# two_tone__2.net
KiCad netlist of a schematic drawn in EAGLE
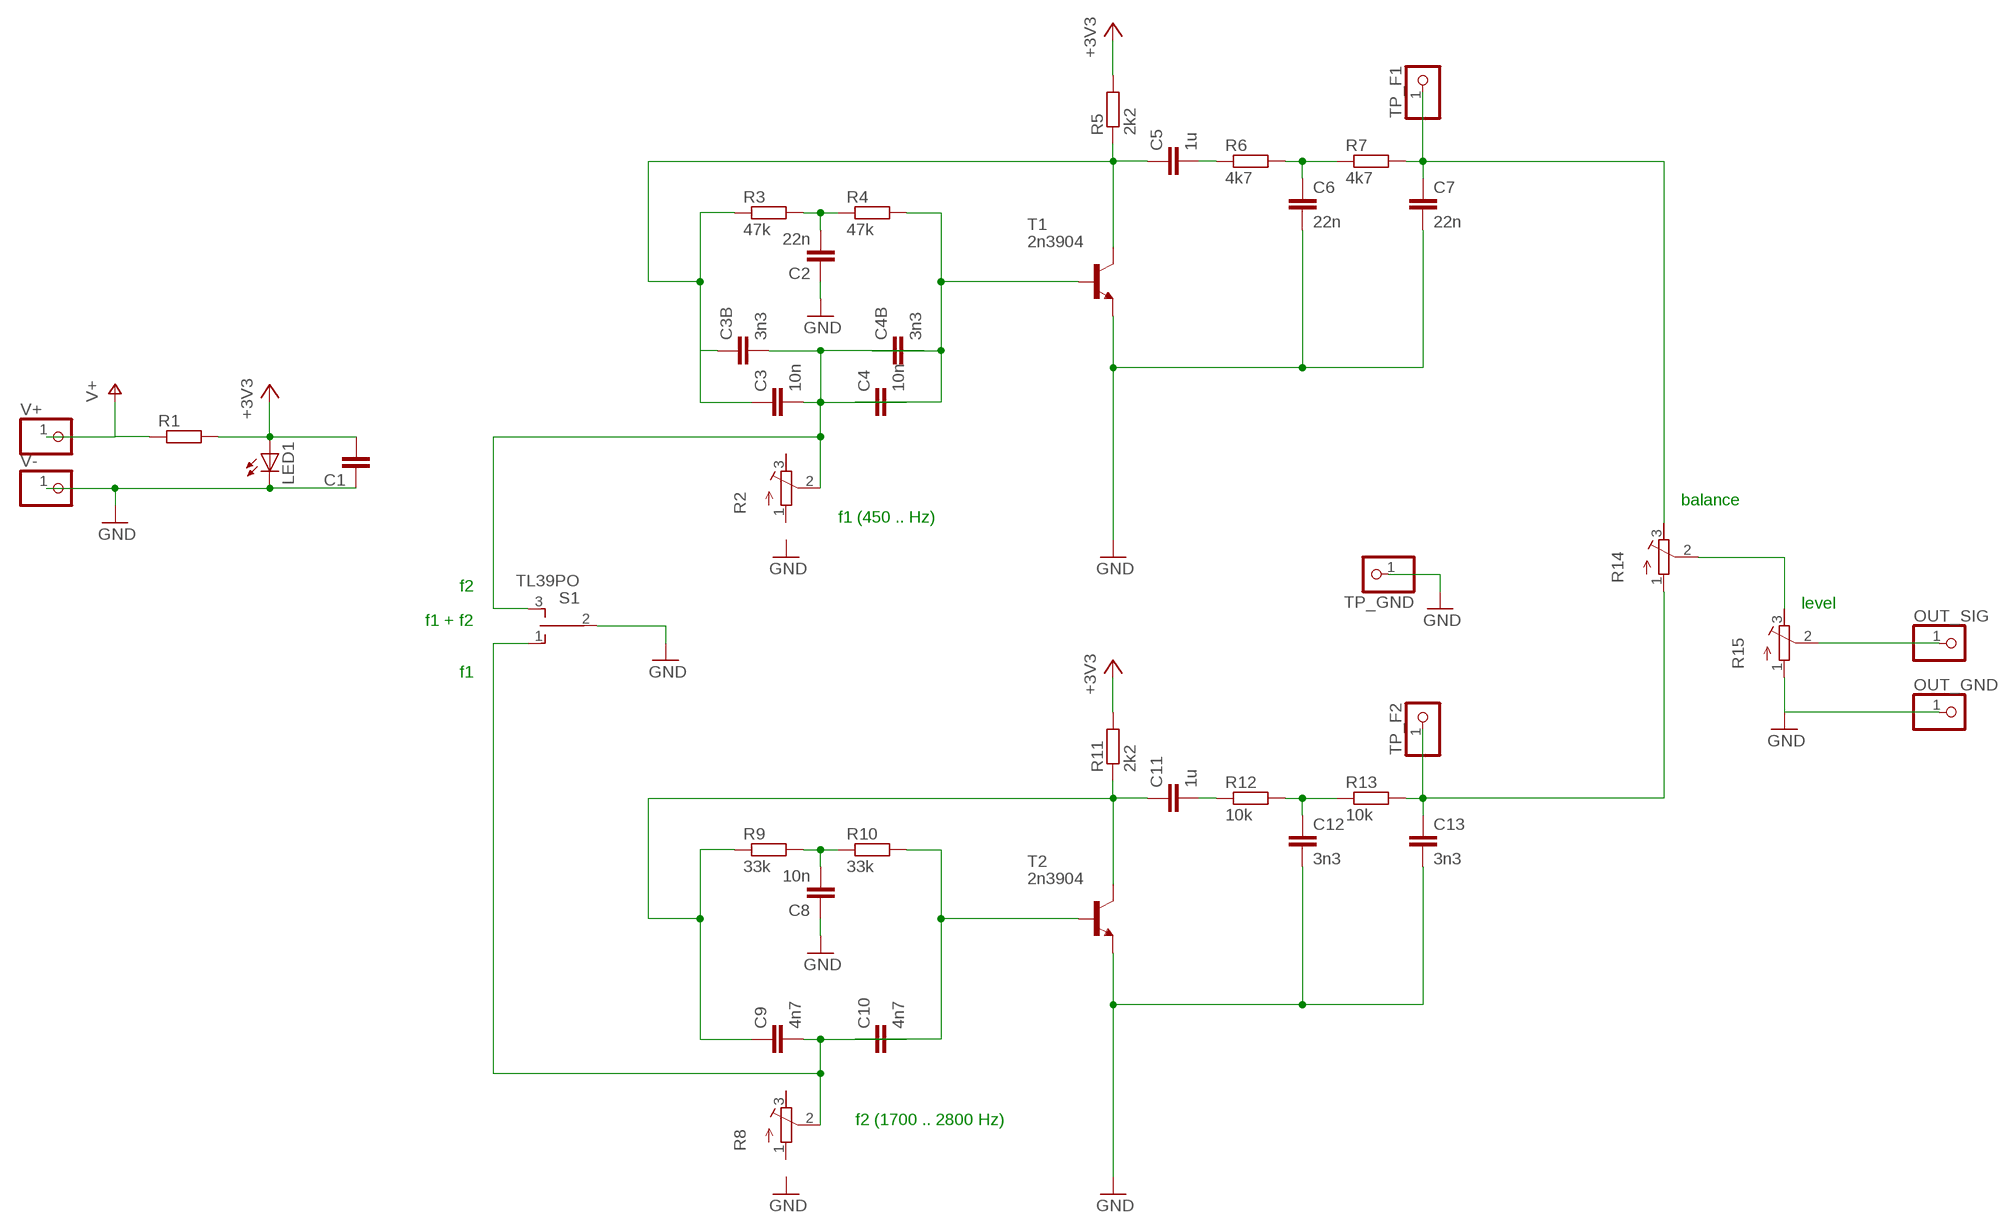
[diagram p0: schematic, sheet 1]

(export (version "E")
  (design (tool "Eeschema 10.0.6"))
  (components
    (comp (ref "C1")
      (value "C-EU025_050-025X075")
      (footprint "eagle-import:C025_050-025X075")
      (libsource (lib "eagle-import") (part "C-EU025_050-025X075"))
    )
    (comp (ref "C2")
      (value "22n")
      (footprint "eagle-import:C025_050-025X075")
      (libsource (lib "eagle-import") (part "C-EU025_050-025X075"))
    )
    (comp (ref "C3")
      (value "10n")
      (footprint "eagle-import:C025_050-025X075")
      (libsource (lib "eagle-import") (part "C-EU025_050-025X075"))
    )
    (comp (ref "C3B")
      (value "3n3")
      (footprint "eagle-import:C025_050-025X075")
      (libsource (lib "eagle-import") (part "C-EU025_050-025X075"))
    )
    (comp (ref "C4")
      (value "10n")
      (footprint "eagle-import:C025_050-025X075")
      (libsource (lib "eagle-import") (part "C-EU025_050-025X075"))
    )
    (comp (ref "C4B")
      (value "3n3")
      (footprint "eagle-import:C025_050-025X075")
      (libsource (lib "eagle-import") (part "C-EU025_050-025X075"))
    )
    (comp (ref "C5")
      (value "1u")
      (footprint "eagle-import:C025_050-025X075")
      (libsource (lib "eagle-import") (part "C-EU025_050-025X075"))
    )
    (comp (ref "C6")
      (value "22n")
      (footprint "eagle-import:C025_050-025X075")
      (libsource (lib "eagle-import") (part "C-EU025_050-025X075"))
    )
    (comp (ref "C7")
      (value "22n")
      (footprint "eagle-import:C025_050-025X075")
      (libsource (lib "eagle-import") (part "C-EU025_050-025X075"))
    )
    (comp (ref "C8")
      (value "10n")
      (footprint "eagle-import:C025_050-025X075")
      (libsource (lib "eagle-import") (part "C-EU025_050-025X075"))
    )
    (comp (ref "C9")
      (value "4n7")
      (footprint "eagle-import:C025_050-025X075")
      (libsource (lib "eagle-import") (part "C-EU025_050-025X075"))
    )
    (comp (ref "C10")
      (value "4n7")
      (footprint "eagle-import:C025_050-025X075")
      (libsource (lib "eagle-import") (part "C-EU025_050-025X075"))
    )
    (comp (ref "C11")
      (value "1u")
      (footprint "eagle-import:C025_050-025X075")
      (libsource (lib "eagle-import") (part "C-EU025_050-025X075"))
    )
    (comp (ref "C12")
      (value "3n3")
      (footprint "eagle-import:C025_050-025X075")
      (libsource (lib "eagle-import") (part "C-EU025_050-025X075"))
    )
    (comp (ref "C13")
      (value "3n3")
      (footprint "eagle-import:C025_050-025X075")
      (libsource (lib "eagle-import") (part "C-EU025_050-025X075"))
    )
    (comp (ref "LED1")
      (value "LED3MM")
      (footprint "eagle-import:LED3MM")
      (libsource (lib "eagle-import") (part "LED3MM"))
    )
    (comp (ref "OUT_GND")
      (value "PINHD-1X1")
      (footprint "eagle-import:1X01")
      (libsource (lib "eagle-import") (part "PINHD-1X1"))
    )
    (comp (ref "OUT_SIG")
      (value "PINHD-1X1")
      (footprint "eagle-import:1X01")
      (libsource (lib "eagle-import") (part "PINHD-1X1"))
    )
    (comp (ref "R1")
      (value "R-EU_0207/2V")
      (footprint "eagle-import:0207_2V")
      (libsource (lib "eagle-import") (part "R-EU_0207/2V"))
    )
    (comp (ref "R2")
      (value "R-TRIMM64W")
      (footprint "eagle-import:RTRIM64W")
      (libsource (lib "eagle-import") (part "R-TRIMM64W"))
    )
    (comp (ref "R3")
      (value "47k")
      (footprint "eagle-import:0207_10")
      (libsource (lib "eagle-import") (part "R-EU_0207/10"))
    )
    (comp (ref "R4")
      (value "47k")
      (footprint "eagle-import:0207_5V")
      (libsource (lib "eagle-import") (part "R-EU_0207/5V"))
    )
    (comp (ref "R5")
      (value "2k2")
      (footprint "eagle-import:0207_10")
      (libsource (lib "eagle-import") (part "R-EU_0207/10"))
    )
    (comp (ref "R6")
      (value "4k7")
      (footprint "eagle-import:0207_10")
      (libsource (lib "eagle-import") (part "R-EU_0207/10"))
    )
    (comp (ref "R7")
      (value "4k7")
      (footprint "eagle-import:0207_2V")
      (libsource (lib "eagle-import") (part "R-EU_0207/2V"))
    )
    (comp (ref "R8")
      (value "R-TRIMM64W")
      (footprint "eagle-import:RTRIM64W")
      (libsource (lib "eagle-import") (part "R-TRIMM64W"))
    )
    (comp (ref "R9")
      (value "33k")
      (footprint "eagle-import:0207_10")
      (libsource (lib "eagle-import") (part "R-EU_0207/10"))
    )
    (comp (ref "R10")
      (value "33k")
      (footprint "eagle-import:0207_5V")
      (libsource (lib "eagle-import") (part "R-EU_0207/5V"))
    )
    (comp (ref "R11")
      (value "2k2")
      (footprint "eagle-import:0207_10")
      (libsource (lib "eagle-import") (part "R-EU_0207/10"))
    )
    (comp (ref "R12")
      (value "10k")
      (footprint "eagle-import:0207_10")
      (libsource (lib "eagle-import") (part "R-EU_0207/10"))
    )
    (comp (ref "R13")
      (value "10k")
      (footprint "eagle-import:0207_2V")
      (libsource (lib "eagle-import") (part "R-EU_0207/2V"))
    )
    (comp (ref "R14")
      (value "R-TRIMM64W")
      (footprint "eagle-import:RTRIM64W")
      (libsource (lib "eagle-import") (part "R-TRIMM64W"))
    )
    (comp (ref "R15")
      (value "R-TRIMM64W")
      (footprint "eagle-import:RTRIM64W")
      (libsource (lib "eagle-import") (part "R-TRIMM64W"))
    )
    (comp (ref "S1")
      (value "TL39PO")
      (footprint "eagle-import:TL3XPO")
      (libsource (lib "eagle-import") (part "TL39PO"))
    )
    (comp (ref "T1")
      (value "2n3904")
      (footprint "eagle-import:TO92-EBC")
      (libsource (lib "eagle-import") (part "-NPN-TO92-EBC2N3904"))
    )
    (comp (ref "T2")
      (value "2n3904")
      (footprint "eagle-import:TO92-EBC")
      (libsource (lib "eagle-import") (part "-NPN-TO92-EBC2N3904"))
    )
    (comp (ref "TP_F1")
      (value "PINHD-1X1")
      (footprint "eagle-import:1X01")
      (libsource (lib "eagle-import") (part "PINHD-1X1"))
    )
    (comp (ref "TP_F2")
      (value "PINHD-1X1")
      (footprint "eagle-import:1X01")
      (libsource (lib "eagle-import") (part "PINHD-1X1"))
    )
    (comp (ref "TP_GND")
      (value "PINHD-1X1")
      (footprint "eagle-import:1X01")
      (libsource (lib "eagle-import") (part "PINHD-1X1"))
    )
    (comp (ref "V+")
      (value "PINHD-1X1")
      (footprint "eagle-import:1X01")
      (libsource (lib "eagle-import") (part "PINHD-1X1"))
    )
    (comp (ref "V-")
      (value "PINHD-1X1")
      (footprint "eagle-import:1X01")
      (libsource (lib "eagle-import") (part "PINHD-1X1"))
    )
  )
  (nets
    (net (code "1") (name "+3V3") (class "Default")
      (node (ref "C1") (pin "2") (pinfunction "2_2") (pintype "passive"))
      (node (ref "LED1") (pin "A") (pinfunction "A_A") (pintype "passive"))
      (node (ref "R1") (pin "2") (pinfunction "2_2") (pintype "passive"))
      (node (ref "R11") (pin "2") (pinfunction "2_2") (pintype "passive"))
      (node (ref "R5") (pin "2") (pinfunction "2_2") (pintype "passive"))
    )
    (net (code "2") (name "GND") (class "Default")
      (node (ref "C1") (pin "1") (pinfunction "1_1") (pintype "passive"))
      (node (ref "C12") (pin "2") (pinfunction "2_2") (pintype "passive"))
      (node (ref "C13") (pin "2") (pinfunction "2_2") (pintype "passive"))
      (node (ref "C2") (pin "1") (pinfunction "1_1") (pintype "passive"))
      (node (ref "C6") (pin "2") (pinfunction "2_2") (pintype "passive"))
      (node (ref "C7") (pin "2") (pinfunction "2_2") (pintype "passive"))
      (node (ref "C8") (pin "1") (pinfunction "1_1") (pintype "passive"))
      (node (ref "LED1") (pin "K") (pinfunction "C_K") (pintype "passive"))
      (node (ref "OUT_GND") (pin "1") (pinfunction "1_1") (pintype "passive"))
      (node (ref "R15") (pin "1") (pinfunction "E_1") (pintype "passive"))
      (node (ref "S1") (pin "2") (pinfunction "P_2") (pintype "passive"))
      (node (ref "T1") (pin "E") (pinfunction "E_E") (pintype "passive"))
      (node (ref "T2") (pin "E") (pinfunction "E_E") (pintype "passive"))
      (node (ref "TP_GND") (pin "1") (pinfunction "1_1") (pintype "passive"))
      (node (ref "V-") (pin "1") (pinfunction "1_1") (pintype "passive"))
    )
    (net (code "3") (name "Net-(C2-Pad2)") (class "Default")
      (node (ref "C2") (pin "2") (pinfunction "2_2") (pintype "passive"))
      (node (ref "R3") (pin "2") (pinfunction "2_2") (pintype "passive"))
      (node (ref "R4") (pin "1") (pinfunction "1_1") (pintype "passive"))
    )
    (net (code "4") (name "Net-(C3-Pad1)") (class "Default")
      (node (ref "C3") (pin "1") (pinfunction "1_1") (pintype "passive"))
      (node (ref "C3B") (pin "1") (pinfunction "1_1") (pintype "passive"))
      (node (ref "C5") (pin "1") (pinfunction "1_1") (pintype "passive"))
      (node (ref "R3") (pin "1") (pinfunction "1_1") (pintype "passive"))
      (node (ref "R5") (pin "1") (pinfunction "1_1") (pintype "passive"))
      (node (ref "T1") (pin "C") (pinfunction "C_C") (pintype "passive"))
    )
    (net (code "5") (name "Net-(C4-Pad1)") (class "Default")
      (node (ref "C4") (pin "1") (pinfunction "1_1") (pintype "passive"))
      (node (ref "C4B") (pin "1") (pinfunction "1_1") (pintype "passive"))
      (node (ref "R4") (pin "2") (pinfunction "2_2") (pintype "passive"))
      (node (ref "T1") (pin "B") (pinfunction "B_B") (pintype "passive"))
    )
    (net (code "6") (name "Net-(C5-Pad2)") (class "Default")
      (node (ref "C5") (pin "2") (pinfunction "2_2") (pintype "passive"))
      (node (ref "R6") (pin "1") (pinfunction "1_1") (pintype "passive"))
    )
    (net (code "7") (name "Net-(C6-Pad1)") (class "Default")
      (node (ref "C6") (pin "1") (pinfunction "1_1") (pintype "passive"))
      (node (ref "R6") (pin "2") (pinfunction "2_2") (pintype "passive"))
      (node (ref "R7") (pin "1") (pinfunction "1_1") (pintype "passive"))
    )
    (net (code "8") (name "Net-(C8-Pad2)") (class "Default")
      (node (ref "C8") (pin "2") (pinfunction "2_2") (pintype "passive"))
      (node (ref "R10") (pin "1") (pinfunction "1_1") (pintype "passive"))
      (node (ref "R9") (pin "2") (pinfunction "2_2") (pintype "passive"))
    )
    (net (code "9") (name "Net-(C10-Pad1)") (class "Default")
      (node (ref "C10") (pin "1") (pinfunction "1_1") (pintype "passive"))
      (node (ref "R10") (pin "2") (pinfunction "2_2") (pintype "passive"))
      (node (ref "T2") (pin "B") (pinfunction "B_B") (pintype "passive"))
    )
    (net (code "10") (name "Net-(C11-Pad1)") (class "Default")
      (node (ref "C11") (pin "1") (pinfunction "1_1") (pintype "passive"))
      (node (ref "C9") (pin "1") (pinfunction "1_1") (pintype "passive"))
      (node (ref "R11") (pin "1") (pinfunction "1_1") (pintype "passive"))
      (node (ref "R9") (pin "1") (pinfunction "1_1") (pintype "passive"))
      (node (ref "T2") (pin "C") (pinfunction "C_C") (pintype "passive"))
    )
    (net (code "11") (name "Net-(C11-Pad2)") (class "Default")
      (node (ref "C11") (pin "2") (pinfunction "2_2") (pintype "passive"))
      (node (ref "R12") (pin "1") (pinfunction "1_1") (pintype "passive"))
    )
    (net (code "12") (name "Net-(C12-Pad1)") (class "Default")
      (node (ref "C12") (pin "1") (pinfunction "1_1") (pintype "passive"))
      (node (ref "R12") (pin "2") (pinfunction "2_2") (pintype "passive"))
      (node (ref "R13") (pin "1") (pinfunction "1_1") (pintype "passive"))
    )
    (net (code "13") (name "Net-(R2-S)") (class "Default")
      (node (ref "C3") (pin "2") (pinfunction "2_2") (pintype "passive"))
      (node (ref "C3B") (pin "2") (pinfunction "2_2") (pintype "passive"))
      (node (ref "C4") (pin "2") (pinfunction "2_2") (pintype "passive"))
      (node (ref "C4B") (pin "2") (pinfunction "2_2") (pintype "passive"))
      (node (ref "R2") (pin "2") (pinfunction "S_2") (pintype "passive"))
      (node (ref "S1") (pin "3") (pinfunction "S_3") (pintype "passive"))
    )
    (net (code "14") (name "Net-(R8-S)") (class "Default")
      (node (ref "C10") (pin "2") (pinfunction "2_2") (pintype "passive"))
      (node (ref "C9") (pin "2") (pinfunction "2_2") (pintype "passive"))
      (node (ref "R8") (pin "2") (pinfunction "S_2") (pintype "passive"))
      (node (ref "S1") (pin "1") (pinfunction "O_1") (pintype "passive"))
    )
    (net (code "15") (name "Net-(R14-A)") (class "Default")
      (node (ref "C7") (pin "1") (pinfunction "1_1") (pintype "passive"))
      (node (ref "R14") (pin "3") (pinfunction "A_3") (pintype "passive"))
      (node (ref "R7") (pin "2") (pinfunction "2_2") (pintype "passive"))
      (node (ref "TP_F1") (pin "1") (pinfunction "1_1") (pintype "passive"))
    )
    (net (code "16") (name "Net-(R14-E)") (class "Default")
      (node (ref "C13") (pin "1") (pinfunction "1_1") (pintype "passive"))
      (node (ref "R13") (pin "2") (pinfunction "2_2") (pintype "passive"))
      (node (ref "R14") (pin "1") (pinfunction "E_1") (pintype "passive"))
      (node (ref "TP_F2") (pin "1") (pinfunction "1_1") (pintype "passive"))
    )
    (net (code "17") (name "Net-(R14-S)") (class "Default")
      (node (ref "R14") (pin "2") (pinfunction "S_2") (pintype "passive"))
      (node (ref "R15") (pin "3") (pinfunction "A_3") (pintype "passive"))
    )
    (net (code "18") (name "Net-(R15-S)") (class "Default")
      (node (ref "OUT_SIG") (pin "1") (pinfunction "1_1") (pintype "passive"))
      (node (ref "R15") (pin "2") (pinfunction "S_2") (pintype "passive"))
    )
    (net (code "19") (name "V+") (class "Default")
      (node (ref "R1") (pin "1") (pinfunction "1_1") (pintype "passive"))
      (node (ref "V+") (pin "1") (pinfunction "1_1") (pintype "passive"))
    )
    (net (code "20") (name "unconnected-(R2-A-Pad3)") (class "Default")
      (node (ref "R2") (pin "3") (pinfunction "A_3") (pintype "passive"))
    )
    (net (code "21") (name "unconnected-(R2-E-Pad1)") (class "Default")
      (node (ref "R2") (pin "1") (pinfunction "E_1") (pintype "passive"))
    )
    (net (code "22") (name "unconnected-(R8-A-Pad3)") (class "Default")
      (node (ref "R8") (pin "3") (pinfunction "A_3") (pintype "passive"))
    )
    (net (code "23") (name "unconnected-(R8-E-Pad1)") (class "Default")
      (node (ref "R8") (pin "1") (pinfunction "E_1") (pintype "passive"))
    )
  )
)
